# arduino_board_1iter.net
KiCad netlist of a schematic drawn in EAGLE
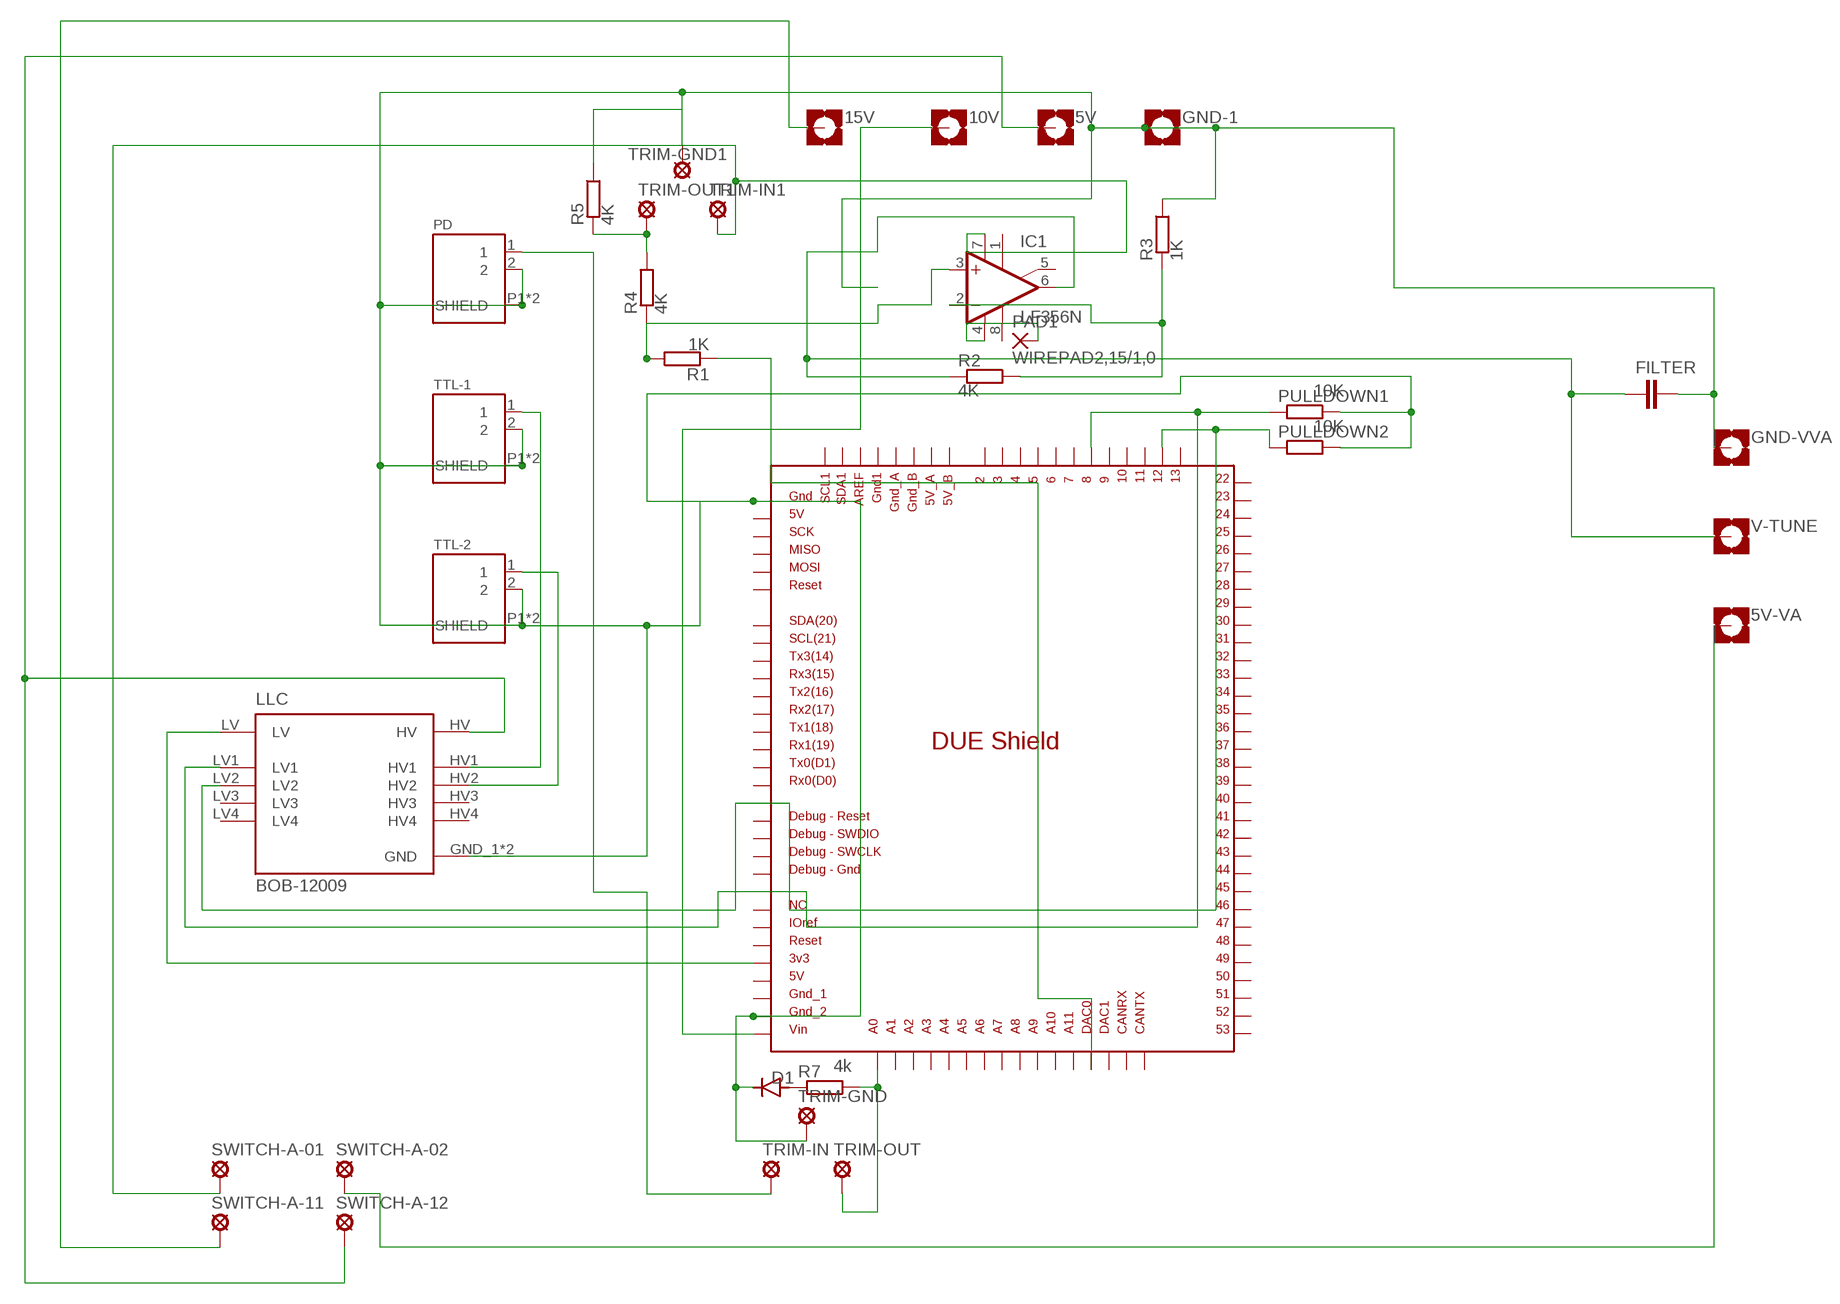
[diagram p0: schematic, sheet 1]

(export (version "E")
  (design (tool "Eeschema 10.0.6"))
  (components
    (comp (ref "5V")
      (value "MOUNT-PAD-SQUARE2.8")
      (footprint "eagle-import:2,8-PAD-SQUARE")
      (libsource (lib "eagle-import") (part "MOUNT-PAD-SQUARE2.8"))
    )
    (comp (ref "5V-VA")
      (value "MOUNT-PAD-SQUARE2.8")
      (footprint "eagle-import:2,8-PAD-SQUARE")
      (libsource (lib "eagle-import") (part "MOUNT-PAD-SQUARE2.8"))
    )
    (comp (ref "10V")
      (value "MOUNT-PAD-SQUARE2.8")
      (footprint "eagle-import:2,8-PAD-SQUARE")
      (libsource (lib "eagle-import") (part "MOUNT-PAD-SQUARE2.8"))
    )
    (comp (ref "15V")
      (value "MOUNT-PAD-SQUARE2.8")
      (footprint "eagle-import:2,8-PAD-SQUARE")
      (libsource (lib "eagle-import") (part "MOUNT-PAD-SQUARE2.8"))
    )
    (comp (ref "D1")
      (value "BA243A")
      (footprint "eagle-import:DO35-10")
      (libsource (lib "eagle-import") (part "BA243A"))
    )
    (comp (ref "FILTER")
      (value "C-EUC1812K")
      (footprint "eagle-import:C1812K")
      (libsource (lib "eagle-import") (part "C-EUC1812K"))
    )
    (comp (ref "GND-1")
      (value "MOUNT-PAD-SQUARE2.8")
      (footprint "eagle-import:2,8-PAD-SQUARE")
      (libsource (lib "eagle-import") (part "MOUNT-PAD-SQUARE2.8"))
    )
    (comp (ref "GND-VVA")
      (value "MOUNT-PAD-SQUARE2.8")
      (footprint "eagle-import:2,8-PAD-SQUARE")
      (libsource (lib "eagle-import") (part "MOUNT-PAD-SQUARE2.8"))
    )
    (comp (ref "IC1")
      (value "LF356N")
      (footprint "eagle-import:DIL08")
      (libsource (lib "eagle-import") (part "LF356N"))
    )
    (comp (ref "LLC")
      (value "BOB-12009")
      (footprint "eagle-import:CONV_BOB-12009")
      (fields (field (name "MF") "SparkFun"))
      (libsource (lib "eagle-import") (part "BOB-12009"))
    )
    (comp (ref "PAD1")
      (value "WIREPAD2,15/1,0")
      (footprint "eagle-import:2,15_1,0")
      (libsource (lib "eagle-import") (part "WIREPAD2,15/1,0"))
    )
    (comp (ref "PD")
      (value "1-1337543-0")
      (footprint "eagle-import:CONN_1-1337543-0")
      (fields (field (name "DIGI-KEY_PART_NUMBER") "A97553-ND") (field (name "MF") "TE Connectivity"))
      (libsource (lib "eagle-import") (part "1-1337543-0"))
    )
    (comp (ref "PULLDOWN1")
      (value "10K")
      (footprint "eagle-import:SMS-0")
      (libsource (lib "eagle-import") (part "SMS-0"))
    )
    (comp (ref "PULLDOWN2")
      (value "10K")
      (footprint "eagle-import:SMS-0")
      (libsource (lib "eagle-import") (part "SMS-0"))
    )
    (comp (ref "R1")
      (value "1K")
      (footprint "eagle-import:SMS-0")
      (libsource (lib "eagle-import") (part "SMS-0"))
    )
    (comp (ref "R2")
      (value "4K")
      (footprint "eagle-import:SMS-0")
      (libsource (lib "eagle-import") (part "SMS-0"))
    )
    (comp (ref "R3")
      (value "1K")
      (footprint "eagle-import:SMS-0")
      (libsource (lib "eagle-import") (part "SMS-0"))
    )
    (comp (ref "R4")
      (value "4K")
      (footprint "eagle-import:SMS-0")
      (libsource (lib "eagle-import") (part "SMS-0"))
    )
    (comp (ref "R5")
      (value "4K")
      (footprint "eagle-import:SMS-0")
      (libsource (lib "eagle-import") (part "SMS-0"))
    )
    (comp (ref "R7")
      (value "4k")
      (footprint "eagle-import:SMS-0")
      (libsource (lib "eagle-import") (part "SMS-0"))
    )
    (comp (ref "SWITCH-A-01")
      (value "LSP10")
      (footprint "eagle-import:LSP10")
      (libsource (lib "eagle-import") (part "LSP10"))
    )
    (comp (ref "SWITCH-A-02")
      (value "LSP10")
      (footprint "eagle-import:LSP10")
      (libsource (lib "eagle-import") (part "LSP10"))
    )
    (comp (ref "SWITCH-A-11")
      (value "LSP10")
      (footprint "eagle-import:LSP10")
      (libsource (lib "eagle-import") (part "LSP10"))
    )
    (comp (ref "SWITCH-A-12")
      (value "LSP10")
      (footprint "eagle-import:LSP10")
      (libsource (lib "eagle-import") (part "LSP10"))
    )
    (comp (ref "TRIM-GND")
      (value "LSP10")
      (footprint "eagle-import:LSP10")
      (libsource (lib "eagle-import") (part "LSP10"))
    )
    (comp (ref "TRIM-GND1")
      (value "LSP10")
      (footprint "eagle-import:LSP10")
      (libsource (lib "eagle-import") (part "LSP10"))
    )
    (comp (ref "TRIM-IN")
      (value "LSP10")
      (footprint "eagle-import:LSP10")
      (libsource (lib "eagle-import") (part "LSP10"))
    )
    (comp (ref "TRIM-IN1")
      (value "LSP10")
      (footprint "eagle-import:LSP10")
      (libsource (lib "eagle-import") (part "LSP10"))
    )
    (comp (ref "TRIM-OUT")
      (value "LSP10")
      (footprint "eagle-import:LSP10")
      (libsource (lib "eagle-import") (part "LSP10"))
    )
    (comp (ref "TRIM-OUT1")
      (value "LSP10")
      (footprint "eagle-import:LSP10")
      (libsource (lib "eagle-import") (part "LSP10"))
    )
    (comp (ref "TTL-1")
      (value "1-1337543-0")
      (footprint "eagle-import:CONN_1-1337543-0")
      (fields (field (name "DIGI-KEY_PART_NUMBER") "A97553-ND") (field (name "MF") "TE Connectivity"))
      (libsource (lib "eagle-import") (part "1-1337543-0"))
    )
    (comp (ref "TTL-2")
      (value "1-1337543-0")
      (footprint "eagle-import:CONN_1-1337543-0")
      (fields (field (name "DIGI-KEY_PART_NUMBER") "A97553-ND") (field (name "MF") "TE Connectivity"))
      (libsource (lib "eagle-import") (part "1-1337543-0"))
    )
    (comp (ref "U$1")
      (value "DUE(NORMAL)")
      (footprint "eagle-import:DUE(NORMAL)")
      (libsource (lib "eagle-import") (part "DUE(NORMAL)"))
    )
    (comp (ref "V-TUNE")
      (value "MOUNT-PAD-SQUARE2.8")
      (footprint "eagle-import:2,8-PAD-SQUARE")
      (libsource (lib "eagle-import") (part "MOUNT-PAD-SQUARE2.8"))
    )
  )
  (nets
    (net (code "1") (name "Net-(5V-MOUNT)") (class "Default")
      (node (ref "5V") (pin "B2,8") (pinfunction "MOUNT_B2,8") (pintype "passive"))
      (node (ref "LLC") (pin "HV") (pinfunction "HV_HV") (pintype "bidirectional"))
      (node (ref "SWITCH-A-12") (pin "MP") (pinfunction "MP_MP") (pintype "passive"))
    )
    (net (code "2") (name "Net-(5V-VA-MOUNT)") (class "Default")
      (node (ref "5V-VA") (pin "B2,8") (pinfunction "MOUNT_B2,8") (pintype "passive"))
      (node (ref "SWITCH-A-02") (pin "MP") (pinfunction "MP_MP") (pintype "passive"))
    )
    (net (code "3") (name "Net-(10V-MOUNT)") (class "Default")
      (node (ref "10V") (pin "B2,8") (pinfunction "MOUNT_B2,8") (pintype "passive"))
      (node (ref "U$1") (pin "VIN") (pinfunction "VIN_VIN") (pintype "bidirectional"))
    )
    (net (code "4") (name "Net-(15V-MOUNT)") (class "Default")
      (node (ref "15V") (pin "B2,8") (pinfunction "MOUNT_B2,8") (pintype "passive"))
      (node (ref "SWITCH-A-11") (pin "MP") (pinfunction "MP_MP") (pintype "passive"))
    )
    (net (code "5") (name "Net-(D1-PadA)") (class "Default")
      (node (ref "D1") (pin "A") (pinfunction "A_A") (pintype "passive"))
      (node (ref "R7") (pin "2") (pinfunction "2_2") (pintype "passive"))
    )
    (net (code "6") (name "Net-(GND-1-MOUNT)") (class "Default")
      (node (ref "D1") (pin "C") (pinfunction "C_C") (pintype "passive"))
      (node (ref "FILTER") (pin "2") (pinfunction "2_2") (pintype "passive"))
      (node (ref "GND-1") (pin "B2,8") (pinfunction "MOUNT_B2,8") (pintype "passive"))
      (node (ref "GND-VVA") (pin "B2,8") (pinfunction "MOUNT_B2,8") (pintype "passive"))
      (node (ref "LLC") (pin "GND_1") (pinfunction "GND_GND_1") (pintype "power_in"))
      (node (ref "LLC") (pin "GND_2") (pinfunction "GND_GND_2") (pintype "power_in"))
      (node (ref "PD") (pin "2") (pinfunction "2_2") (pintype "passive"))
      (node (ref "PD") (pin "P1") (pinfunction "SHIELD_P1") (pintype "passive"))
      (node (ref "PD") (pin "P2") (pinfunction "SHIELD_P2") (pintype "passive"))
      (node (ref "PULLDOWN1") (pin "1") (pinfunction "1_1") (pintype "passive"))
      (node (ref "PULLDOWN2") (pin "1") (pinfunction "1_1") (pintype "passive"))
      (node (ref "R3") (pin "1") (pinfunction "1_1") (pintype "passive"))
      (node (ref "R5") (pin "1") (pinfunction "1_1") (pintype "passive"))
      (node (ref "TRIM-GND") (pin "MP") (pinfunction "MP_MP") (pintype "passive"))
      (node (ref "TRIM-GND1") (pin "MP") (pinfunction "MP_MP") (pintype "passive"))
      (node (ref "TTL-1") (pin "2") (pinfunction "2_2") (pintype "passive"))
      (node (ref "TTL-1") (pin "P1") (pinfunction "SHIELD_P1") (pintype "passive"))
      (node (ref "TTL-1") (pin "P2") (pinfunction "SHIELD_P2") (pintype "passive"))
      (node (ref "TTL-2") (pin "2") (pinfunction "2_2") (pintype "passive"))
      (node (ref "TTL-2") (pin "P1") (pinfunction "SHIELD_P1") (pintype "passive"))
      (node (ref "TTL-2") (pin "P2") (pinfunction "SHIELD_P2") (pintype "passive"))
      (node (ref "U$1") (pin "5V_ICSP") (pinfunction "5V_ICSP_5V_ICSP") (pintype "bidirectional"))
      (node (ref "U$1") (pin "GND_2") (pinfunction "GND_2_GND_2") (pintype "bidirectional"))
    )
    (net (code "7") (name "Net-(IC1-+IN)") (class "Default")
      (node (ref "IC1") (pin "3") (pinfunction "+IN_3") (pintype "input"))
      (node (ref "R1") (pin "1") (pinfunction "1_1") (pintype "passive"))
      (node (ref "R4") (pin "2") (pinfunction "2_2") (pintype "passive"))
    )
    (net (code "8") (name "Net-(IC1--IN)") (class "Default")
      (node (ref "IC1") (pin "2") (pinfunction "-IN_2") (pintype "input"))
      (node (ref "R2") (pin "1") (pinfunction "1_1") (pintype "passive"))
      (node (ref "R3") (pin "2") (pinfunction "2_2") (pintype "passive"))
    )
    (net (code "9") (name "Net-(IC1-OUT)") (class "Default")
      (node (ref "FILTER") (pin "1") (pinfunction "1_1") (pintype "passive"))
      (node (ref "IC1") (pin "6") (pinfunction "OUT_6") (pintype "output"))
      (node (ref "R2") (pin "2") (pinfunction "2_2") (pintype "passive"))
      (node (ref "V-TUNE") (pin "B2,8") (pinfunction "MOUNT_B2,8") (pintype "passive"))
    )
    (net (code "10") (name "Net-(IC1-V+)") (class "Default")
      (node (ref "IC1") (pin "7") (pinfunction "V+_7") (pintype "power_in"))
      (node (ref "SWITCH-A-01") (pin "MP") (pinfunction "MP_MP") (pintype "passive"))
      (node (ref "TRIM-IN1") (pin "MP") (pinfunction "MP_MP") (pintype "passive"))
    )
    (net (code "11") (name "Net-(IC1-V-)") (class "Default")
      (node (ref "IC1") (pin "4") (pinfunction "V-_4") (pintype "power_in"))
      (node (ref "PAD1") (pin "1") (pinfunction "P_1") (pintype "passive"))
    )
    (net (code "12") (name "Net-(LLC-PadHV1)") (class "Default")
      (node (ref "LLC") (pin "HV1") (pinfunction "HV1_HV1") (pintype "bidirectional"))
      (node (ref "TTL-1") (pin "1") (pinfunction "1_1") (pintype "passive"))
    )
    (net (code "13") (name "Net-(LLC-PadHV2)") (class "Default")
      (node (ref "LLC") (pin "HV2") (pinfunction "HV2_HV2") (pintype "bidirectional"))
      (node (ref "TTL-2") (pin "1") (pinfunction "1_1") (pintype "passive"))
    )
    (net (code "14") (name "Net-(LLC-PadLV)") (class "Default")
      (node (ref "LLC") (pin "LV") (pinfunction "LV_LV") (pintype "bidirectional"))
      (node (ref "U$1") (pin "3V3") (pinfunction "3V3_3V3") (pintype "bidirectional"))
    )
    (net (code "15") (name "Net-(LLC-PadLV1)") (class "Default")
      (node (ref "LLC") (pin "LV1") (pinfunction "LV1_LV1") (pintype "bidirectional"))
      (node (ref "PULLDOWN1") (pin "2") (pinfunction "2_2") (pintype "passive"))
      (node (ref "U$1") (pin "8") (pinfunction "8_8") (pintype "bidirectional"))
    )
    (net (code "16") (name "Net-(LLC-PadLV2)") (class "Default")
      (node (ref "LLC") (pin "LV2") (pinfunction "LV2_LV2") (pintype "bidirectional"))
      (node (ref "PULLDOWN2") (pin "2") (pinfunction "2_2") (pintype "passive"))
      (node (ref "U$1") (pin "12") (pinfunction "12_12") (pintype "bidirectional"))
    )
    (net (code "17") (name "Net-(PD-Pad1)") (class "Default")
      (node (ref "PD") (pin "1") (pinfunction "1_1") (pintype "passive"))
      (node (ref "TRIM-IN") (pin "MP") (pinfunction "MP_MP") (pintype "passive"))
    )
    (net (code "18") (name "Net-(R1-Pad2)") (class "Default")
      (node (ref "R1") (pin "2") (pinfunction "2_2") (pintype "passive"))
      (node (ref "U$1") (pin "DAC0") (pinfunction "DAC0_DAC0") (pintype "bidirectional"))
    )
    (net (code "19") (name "Net-(R4-Pad1)") (class "Default")
      (node (ref "R4") (pin "1") (pinfunction "1_1") (pintype "passive"))
      (node (ref "R5") (pin "2") (pinfunction "2_2") (pintype "passive"))
      (node (ref "TRIM-OUT1") (pin "MP") (pinfunction "MP_MP") (pintype "passive"))
    )
    (net (code "20") (name "Net-(R7-Pad1)") (class "Default")
      (node (ref "R7") (pin "1") (pinfunction "1_1") (pintype "passive"))
      (node (ref "TRIM-OUT") (pin "MP") (pinfunction "MP_MP") (pintype "passive"))
      (node (ref "U$1") (pin "A0") (pinfunction "A0_A0") (pintype "bidirectional"))
    )
    (net (code "21") (name "unconnected-(IC1-ON1-Pad1)") (class "Default")
      (node (ref "IC1") (pin "1") (pinfunction "ON1_1") (pintype "passive"))
    )
    (net (code "22") (name "unconnected-(IC1-ON2-Pad5)") (class "Default")
      (node (ref "IC1") (pin "5") (pinfunction "ON2_5") (pintype "passive"))
    )
    (net (code "23") (name "unconnected-(IC1-OPT-Pad8)") (class "Default")
      (node (ref "IC1") (pin "8") (pinfunction "OPT_8") (pintype "passive"))
    )
    (net (code "24") (name "unconnected-(LLC-PadHV3)") (class "Default")
      (node (ref "LLC") (pin "HV3") (pinfunction "HV3_HV3") (pintype "bidirectional"))
    )
    (net (code "25") (name "unconnected-(LLC-PadHV4)") (class "Default")
      (node (ref "LLC") (pin "HV4") (pinfunction "HV4_HV4") (pintype "bidirectional"))
    )
    (net (code "26") (name "unconnected-(LLC-PadLV3)") (class "Default")
      (node (ref "LLC") (pin "LV3") (pinfunction "LV3_LV3") (pintype "bidirectional"))
    )
    (net (code "27") (name "unconnected-(LLC-PadLV4)") (class "Default")
      (node (ref "LLC") (pin "LV4") (pinfunction "LV4_LV4") (pintype "bidirectional"))
    )
    (net (code "28") (name "unconnected-(U$1-Pad2)") (class "Default")
      (node (ref "U$1") (pin "2") (pinfunction "2_2") (pintype "bidirectional"))
    )
    (net (code "29") (name "unconnected-(U$1-Pad3)") (class "Default")
      (node (ref "U$1") (pin "3") (pinfunction "3_3") (pintype "bidirectional"))
    )
    (net (code "30") (name "unconnected-(U$1-Pad4)") (class "Default")
      (node (ref "U$1") (pin "4") (pinfunction "4_4") (pintype "bidirectional"))
    )
    (net (code "31") (name "unconnected-(U$1-Pad5)") (class "Default")
      (node (ref "U$1") (pin "5") (pinfunction "5_5") (pintype "bidirectional"))
    )
    (net (code "32") (name "unconnected-(U$1-Pad5V)") (class "Default")
      (node (ref "U$1") (pin "5V") (pinfunction "5V_5V") (pintype "bidirectional"))
    )
    (net (code "33") (name "unconnected-(U$1-Pad5V_A)") (class "Default")
      (node (ref "U$1") (pin "5V_A") (pinfunction "5V_A_5V_A") (pintype "bidirectional"))
    )
    (net (code "34") (name "unconnected-(U$1-Pad5V_B)") (class "Default")
      (node (ref "U$1") (pin "5V_B") (pinfunction "5V_B_5V_B") (pintype "bidirectional"))
    )
    (net (code "35") (name "unconnected-(U$1-Pad6)") (class "Default")
      (node (ref "U$1") (pin "6") (pinfunction "6_6") (pintype "bidirectional"))
    )
    (net (code "36") (name "unconnected-(U$1-Pad7)") (class "Default")
      (node (ref "U$1") (pin "7") (pinfunction "7_7") (pintype "bidirectional"))
    )
    (net (code "37") (name "unconnected-(U$1-Pad9)") (class "Default")
      (node (ref "U$1") (pin "9") (pinfunction "9_9") (pintype "bidirectional"))
    )
    (net (code "38") (name "unconnected-(U$1-Pad10)") (class "Default")
      (node (ref "U$1") (pin "10") (pinfunction "10_10") (pintype "bidirectional"))
    )
    (net (code "39") (name "unconnected-(U$1-Pad11)") (class "Default")
      (node (ref "U$1") (pin "11") (pinfunction "11_11") (pintype "bidirectional"))
    )
    (net (code "40") (name "unconnected-(U$1-Pad13)") (class "Default")
      (node (ref "U$1") (pin "13") (pinfunction "13_13") (pintype "bidirectional"))
    )
    (net (code "41") (name "unconnected-(U$1-Pad22)") (class "Default")
      (node (ref "U$1") (pin "22") (pinfunction "22_22") (pintype "bidirectional"))
    )
    (net (code "42") (name "unconnected-(U$1-Pad23)") (class "Default")
      (node (ref "U$1") (pin "23") (pinfunction "23_23") (pintype "bidirectional"))
    )
    (net (code "43") (name "unconnected-(U$1-Pad24)") (class "Default")
      (node (ref "U$1") (pin "24") (pinfunction "24_24") (pintype "bidirectional"))
    )
    (net (code "44") (name "unconnected-(U$1-Pad25)") (class "Default")
      (node (ref "U$1") (pin "25") (pinfunction "25_25") (pintype "bidirectional"))
    )
    (net (code "45") (name "unconnected-(U$1-Pad26)") (class "Default")
      (node (ref "U$1") (pin "26") (pinfunction "26_26") (pintype "bidirectional"))
    )
    (net (code "46") (name "unconnected-(U$1-Pad27)") (class "Default")
      (node (ref "U$1") (pin "27") (pinfunction "27_27") (pintype "bidirectional"))
    )
    (net (code "47") (name "unconnected-(U$1-Pad28)") (class "Default")
      (node (ref "U$1") (pin "28") (pinfunction "28_28") (pintype "bidirectional"))
    )
    (net (code "48") (name "unconnected-(U$1-Pad29)") (class "Default")
      (node (ref "U$1") (pin "29") (pinfunction "29_29") (pintype "bidirectional"))
    )
    (net (code "49") (name "unconnected-(U$1-Pad30)") (class "Default")
      (node (ref "U$1") (pin "30") (pinfunction "30_30") (pintype "bidirectional"))
    )
    (net (code "50") (name "unconnected-(U$1-Pad31)") (class "Default")
      (node (ref "U$1") (pin "31") (pinfunction "31_31") (pintype "bidirectional"))
    )
    (net (code "51") (name "unconnected-(U$1-Pad32)") (class "Default")
      (node (ref "U$1") (pin "32") (pinfunction "32_32") (pintype "bidirectional"))
    )
    (net (code "52") (name "unconnected-(U$1-Pad33)") (class "Default")
      (node (ref "U$1") (pin "33") (pinfunction "33_33") (pintype "bidirectional"))
    )
    (net (code "53") (name "unconnected-(U$1-Pad34)") (class "Default")
      (node (ref "U$1") (pin "34") (pinfunction "34_34") (pintype "bidirectional"))
    )
    (net (code "54") (name "unconnected-(U$1-Pad35)") (class "Default")
      (node (ref "U$1") (pin "35") (pinfunction "35_35") (pintype "bidirectional"))
    )
    (net (code "55") (name "unconnected-(U$1-Pad36)") (class "Default")
      (node (ref "U$1") (pin "36") (pinfunction "36_36") (pintype "bidirectional"))
    )
    (net (code "56") (name "unconnected-(U$1-Pad37)") (class "Default")
      (node (ref "U$1") (pin "37") (pinfunction "37_37") (pintype "bidirectional"))
    )
    (net (code "57") (name "unconnected-(U$1-Pad38)") (class "Default")
      (node (ref "U$1") (pin "38") (pinfunction "38_38") (pintype "bidirectional"))
    )
    (net (code "58") (name "unconnected-(U$1-Pad39)") (class "Default")
      (node (ref "U$1") (pin "39") (pinfunction "39_39") (pintype "bidirectional"))
    )
    (net (code "59") (name "unconnected-(U$1-Pad40)") (class "Default")
      (node (ref "U$1") (pin "40") (pinfunction "40_40") (pintype "bidirectional"))
    )
    (net (code "60") (name "unconnected-(U$1-Pad41)") (class "Default")
      (node (ref "U$1") (pin "41") (pinfunction "41_41") (pintype "bidirectional"))
    )
    (net (code "61") (name "unconnected-(U$1-Pad42)") (class "Default")
      (node (ref "U$1") (pin "42") (pinfunction "42_42") (pintype "bidirectional"))
    )
    (net (code "62") (name "unconnected-(U$1-Pad43)") (class "Default")
      (node (ref "U$1") (pin "43") (pinfunction "43_43") (pintype "bidirectional"))
    )
    (net (code "63") (name "unconnected-(U$1-Pad44)") (class "Default")
      (node (ref "U$1") (pin "44") (pinfunction "44_44") (pintype "bidirectional"))
    )
    (net (code "64") (name "unconnected-(U$1-Pad45)") (class "Default")
      (node (ref "U$1") (pin "45") (pinfunction "45_45") (pintype "bidirectional"))
    )
    (net (code "65") (name "unconnected-(U$1-Pad46)") (class "Default")
      (node (ref "U$1") (pin "46") (pinfunction "46_46") (pintype "bidirectional"))
    )
    (net (code "66") (name "unconnected-(U$1-Pad47)") (class "Default")
      (node (ref "U$1") (pin "47") (pinfunction "47_47") (pintype "bidirectional"))
    )
    (net (code "67") (name "unconnected-(U$1-Pad48)") (class "Default")
      (node (ref "U$1") (pin "48") (pinfunction "48_48") (pintype "bidirectional"))
    )
    (net (code "68") (name "unconnected-(U$1-Pad49)") (class "Default")
      (node (ref "U$1") (pin "49") (pinfunction "49_49") (pintype "bidirectional"))
    )
    (net (code "69") (name "unconnected-(U$1-Pad50)") (class "Default")
      (node (ref "U$1") (pin "50") (pinfunction "50_50") (pintype "bidirectional"))
    )
    (net (code "70") (name "unconnected-(U$1-Pad51)") (class "Default")
      (node (ref "U$1") (pin "51") (pinfunction "51_51") (pintype "bidirectional"))
    )
    (net (code "71") (name "unconnected-(U$1-Pad52)") (class "Default")
      (node (ref "U$1") (pin "52") (pinfunction "52_52") (pintype "bidirectional"))
    )
    (net (code "72") (name "unconnected-(U$1-Pad53)") (class "Default")
      (node (ref "U$1") (pin "53") (pinfunction "53_53") (pintype "bidirectional"))
    )
    (net (code "73") (name "unconnected-(U$1-PadA1)") (class "Default")
      (node (ref "U$1") (pin "A1") (pinfunction "A1_A1") (pintype "bidirectional"))
    )
    (net (code "74") (name "unconnected-(U$1-PadA2)") (class "Default")
      (node (ref "U$1") (pin "A2") (pinfunction "A2_A2") (pintype "bidirectional"))
    )
    (net (code "75") (name "unconnected-(U$1-PadA3)") (class "Default")
      (node (ref "U$1") (pin "A3") (pinfunction "A3_A3") (pintype "bidirectional"))
    )
    (net (code "76") (name "unconnected-(U$1-PadA4)") (class "Default")
      (node (ref "U$1") (pin "A4") (pinfunction "A4_A4") (pintype "bidirectional"))
    )
    (net (code "77") (name "unconnected-(U$1-PadA5)") (class "Default")
      (node (ref "U$1") (pin "A5") (pinfunction "A5_A5") (pintype "bidirectional"))
    )
    (net (code "78") (name "unconnected-(U$1-PadA6)") (class "Default")
      (node (ref "U$1") (pin "A6") (pinfunction "A6_A6") (pintype "bidirectional"))
    )
    (net (code "79") (name "unconnected-(U$1-PadA7)") (class "Default")
      (node (ref "U$1") (pin "A7") (pinfunction "A7_A7") (pintype "bidirectional"))
    )
    (net (code "80") (name "unconnected-(U$1-PadA8)") (class "Default")
      (node (ref "U$1") (pin "A8") (pinfunction "A8_A8") (pintype "bidirectional"))
    )
    (net (code "81") (name "unconnected-(U$1-PadA9)") (class "Default")
      (node (ref "U$1") (pin "A9") (pinfunction "A9_A9") (pintype "bidirectional"))
    )
    (net (code "82") (name "unconnected-(U$1-PadA10)") (class "Default")
      (node (ref "U$1") (pin "A10") (pinfunction "A10_A10") (pintype "bidirectional"))
    )
    (net (code "83") (name "unconnected-(U$1-PadA11)") (class "Default")
      (node (ref "U$1") (pin "A11") (pinfunction "A11_A11") (pintype "bidirectional"))
    )
    (net (code "84") (name "unconnected-(U$1-PadAREF)") (class "Default")
      (node (ref "U$1") (pin "AREF") (pinfunction "AREF_AREF") (pintype "bidirectional"))
    )
    (net (code "85") (name "unconnected-(U$1-PadCANRX)") (class "Default")
      (node (ref "U$1") (pin "CANRX") (pinfunction "CANRX_CANRX") (pintype "bidirectional"))
    )
    (net (code "86") (name "unconnected-(U$1-PadCANTX)") (class "Default")
      (node (ref "U$1") (pin "CANTX") (pinfunction "CANTX_CANTX") (pintype "bidirectional"))
    )
    (net (code "87") (name "unconnected-(U$1-PadDAC1)") (class "Default")
      (node (ref "U$1") (pin "DAC1") (pinfunction "DAC1_DAC1") (pintype "bidirectional"))
    )
    (net (code "88") (name "unconnected-(U$1-PadGND1)") (class "Default")
      (node (ref "U$1") (pin "GND1") (pinfunction "GND1_GND1") (pintype "bidirectional"))
    )
    (net (code "89") (name "unconnected-(U$1-PadGND_1)") (class "Default")
      (node (ref "U$1") (pin "GND_1") (pinfunction "GND_1_GND_1") (pintype "bidirectional"))
    )
    (net (code "90") (name "unconnected-(U$1-PadGND_A)") (class "Default")
      (node (ref "U$1") (pin "GND_A") (pinfunction "GND_A_GND_A") (pintype "bidirectional"))
    )
    (net (code "91") (name "unconnected-(U$1-PadGND_B)") (class "Default")
      (node (ref "U$1") (pin "GND_B") (pinfunction "GND_B_GND_B") (pintype "bidirectional"))
    )
    (net (code "92") (name "unconnected-(U$1-PadGND_DEBUG)") (class "Default")
      (node (ref "U$1") (pin "GND_DEBUG") (pinfunction "GND_DEBUG_GND_DEBUG") (pintype "bidirectional"))
    )
    (net (code "93") (name "unconnected-(U$1-PadGND_ICSP)") (class "Default")
      (node (ref "U$1") (pin "GND_ICSP") (pinfunction "GND_ICSP_GND_ICSP") (pintype "bidirectional"))
    )
    (net (code "94") (name "unconnected-(U$1-PadIOREF)") (class "Default")
      (node (ref "U$1") (pin "IOREF") (pinfunction "IOREF_IOREF") (pintype "bidirectional"))
    )
    (net (code "95") (name "unconnected-(U$1-PadMISO_ICSP)") (class "Default")
      (node (ref "U$1") (pin "MISO_ICSP") (pinfunction "MISO_ICSP_MISO_ICSP") (pintype "bidirectional"))
    )
    (net (code "96") (name "unconnected-(U$1-PadMOSI_ICSP)") (class "Default")
      (node (ref "U$1") (pin "MOSI_ICSP") (pinfunction "MOSI_ICSP_MOSI_ICSP") (pintype "bidirectional"))
    )
    (net (code "97") (name "unconnected-(U$1-PadNC)") (class "Default")
      (node (ref "U$1") (pin "NC") (pinfunction "NC_NC") (pintype "bidirectional"))
    )
    (net (code "98") (name "unconnected-(U$1-PadRESET)") (class "Default")
      (node (ref "U$1") (pin "RESET") (pinfunction "RESET_RESET") (pintype "bidirectional"))
    )
    (net (code "99") (name "unconnected-(U$1-PadRESET_DEBUG)") (class "Default")
      (node (ref "U$1") (pin "RESET_DEBUG") (pinfunction "RESET_DEBUG_RESET_DEBUG") (pintype "bidirectional"))
    )
    (net (code "100") (name "unconnected-(U$1-PadRESET_ICSP)") (class "Default")
      (node (ref "U$1") (pin "RESET_ICSP") (pinfunction "RESET_ICSP_RESET_ICSP") (pintype "bidirectional"))
    )
    (net (code "101") (name "unconnected-(U$1-PadRX0)") (class "Default")
      (node (ref "U$1") (pin "RX0") (pinfunction "RX0_RX0") (pintype "bidirectional"))
    )
    (net (code "102") (name "unconnected-(U$1-PadRX1)") (class "Default")
      (node (ref "U$1") (pin "RX1") (pinfunction "RX1_RX1") (pintype "bidirectional"))
    )
    (net (code "103") (name "unconnected-(U$1-PadRX2)") (class "Default")
      (node (ref "U$1") (pin "RX2") (pinfunction "RX2_RX2") (pintype "bidirectional"))
    )
    (net (code "104") (name "unconnected-(U$1-PadRX3)") (class "Default")
      (node (ref "U$1") (pin "RX3") (pinfunction "RX3_RX3") (pintype "bidirectional"))
    )
    (net (code "105") (name "unconnected-(U$1-PadSCK_ICSP)") (class "Default")
      (node (ref "U$1") (pin "SCK_ICSP") (pinfunction "SCK_ICSP_SCK_ICSP") (pintype "bidirectional"))
    )
    (net (code "106") (name "unconnected-(U$1-PadSCL)") (class "Default")
      (node (ref "U$1") (pin "SCL") (pinfunction "SCL_SCL") (pintype "bidirectional"))
    )
    (net (code "107") (name "unconnected-(U$1-PadSCL1)") (class "Default")
      (node (ref "U$1") (pin "SCL1") (pinfunction "SCL1_SCL1") (pintype "bidirectional"))
    )
    (net (code "108") (name "unconnected-(U$1-PadSDA)") (class "Default")
      (node (ref "U$1") (pin "SDA") (pinfunction "SDA_SDA") (pintype "bidirectional"))
    )
    (net (code "109") (name "unconnected-(U$1-PadSDA1)") (class "Default")
      (node (ref "U$1") (pin "SDA1") (pinfunction "SDA1_SDA1") (pintype "bidirectional"))
    )
    (net (code "110") (name "unconnected-(U$1-PadSWCLK_DEBUG)") (class "Default")
      (node (ref "U$1") (pin "SWCLK_DEBUG") (pinfunction "SWCLK_DEBUG_SWCLK_DEBUG") (pintype "bidirectional"))
    )
    (net (code "111") (name "unconnected-(U$1-PadSWDIO_DEBUG)") (class "Default")
      (node (ref "U$1") (pin "SWDIO_DEBUG") (pinfunction "SWDIO_DEBUG_SWDIO_DEBUG") (pintype "bidirectional"))
    )
    (net (code "112") (name "unconnected-(U$1-PadTX0)") (class "Default")
      (node (ref "U$1") (pin "TX0") (pinfunction "TX0_TX0") (pintype "bidirectional"))
    )
    (net (code "113") (name "unconnected-(U$1-PadTX1)") (class "Default")
      (node (ref "U$1") (pin "TX1") (pinfunction "TX1_TX1") (pintype "bidirectional"))
    )
    (net (code "114") (name "unconnected-(U$1-PadTX2)") (class "Default")
      (node (ref "U$1") (pin "TX2") (pinfunction "TX2_TX2") (pintype "bidirectional"))
    )
    (net (code "115") (name "unconnected-(U$1-PadTX3)") (class "Default")
      (node (ref "U$1") (pin "TX3") (pinfunction "TX3_TX3") (pintype "bidirectional"))
    )
  )
)
